# CANBUS_Pendant.net
KiCad netlist of a schematic drawn in Altium Designer
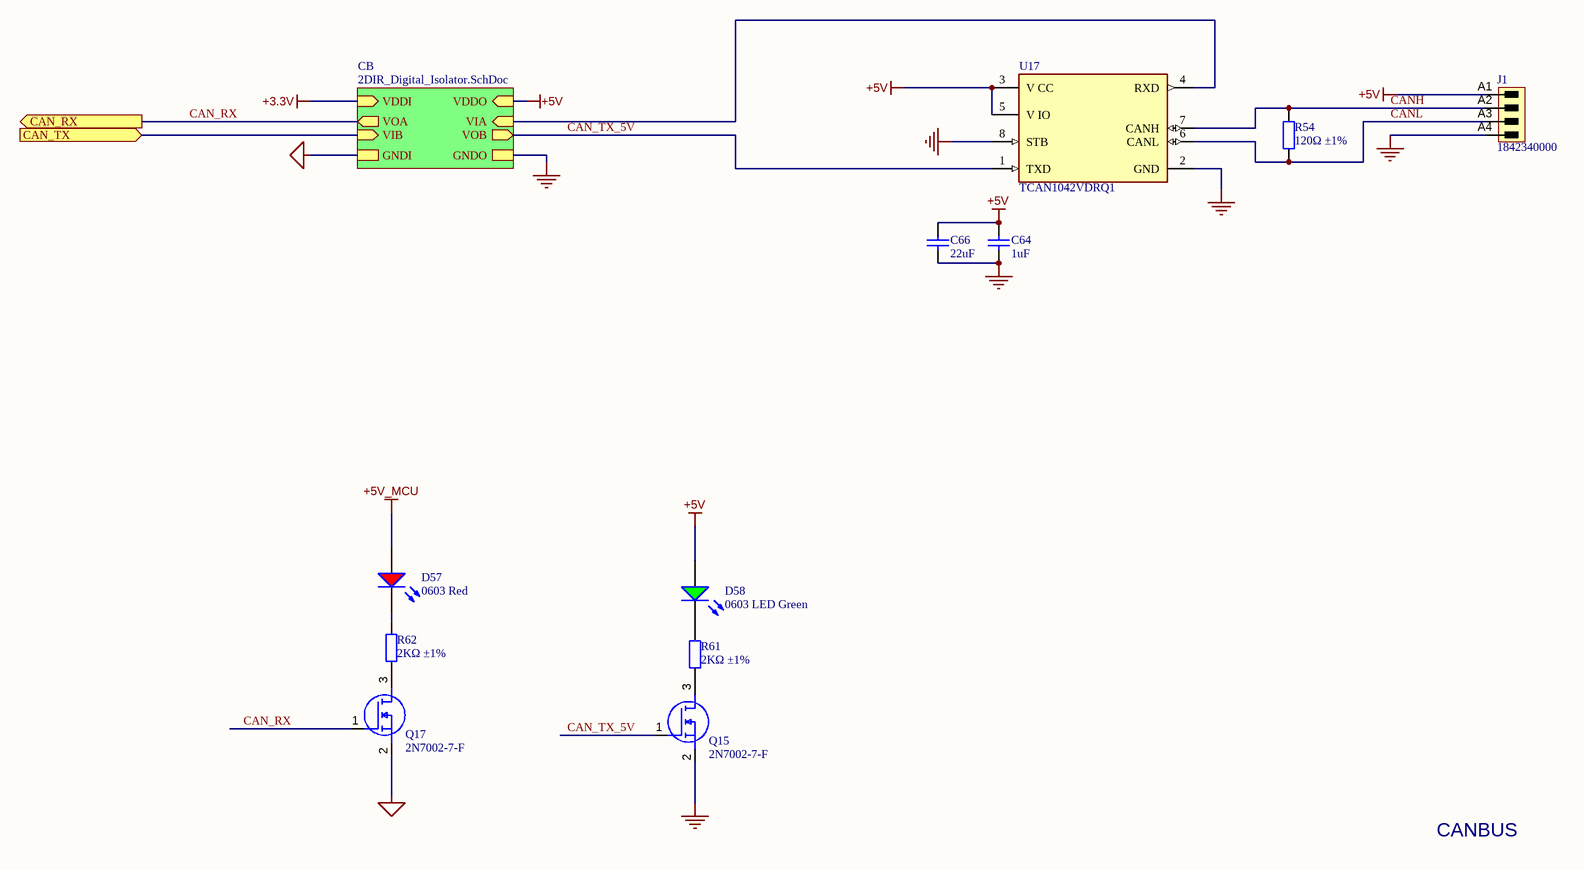
[diagram p0: CANBUS_Pendant.SchDoc]

(export (version "E")
  (design (tool "Eeschema 10.0.6"))
  (components
    (comp (ref "C64")
      (value "1uF")
      (footprint "0603_C")
      (description "Chip capacitors")
      (fields
        (field (name "MANUFACTURER") "Samsung Electro-Mechanics")
        (field (name "MANUFACTURER PART NUMBER") "CL10A105KB8NNNC")
      )
      (libsource (lib "Cap") (part "0603 1uF (105) 10% 50V"))
    )
    (comp (ref "C66")
      (value "22uF")
      (footprint "0603_C")
      (description "Chip capacitors")
      (fields
        (field (name "MANUFACTURER") "Samsung Electro-Mechanics")
        (field (name "PARTNUMBER") "CL10A226MQ8NRNC")
      )
      (libsource (lib "Cap") (part "0603 22uF (226) 20% 6.3V"))
    )
    (comp (ref "D57")
      (value "0603 Red")
      (footprint "0603_LED_S1")
      (fields
        (field (name "MANUFACTURER") "Everlight Elec")
        (field (name "MANUFACTURER PART NUMBER") "19-213SURC/S530-A3/TR8")
      )
      (libsource (lib "Sienci_Labs") (part "19-213SURC/S530-A3/TR8"))
    )
    (comp (ref "D58")
      (value "0603 LED Green")
      (footprint "0603_LED_S1")
      (fields
        (field (name "MANUFACTURER PART NUMBER") "19-217/GHC-YR1S2/3T")
        (field (name "MANUFACTURER") "Everlight Elec")
      )
      (libsource (lib "Sienci_Labs") (part "19-217/GHC-YR1S2/3T"))
    )
    (comp (ref "J1")
      (value "1842340000")
      (footprint "691321100004")
      (description "OMNIMATE Signal - series BL/SL 3.50")
      (libsource (lib "Universal_CNC_Breakout") (part "3.5mm Terminal Header 4p"))
    )
    (comp (ref "Q15")
      (value "2N7002-7-F")
      (footprint "SOT-23(SOT-23-3)")
      (description "60V 115mA 7.5Ω@5V,50mA 370mW N Channel SOT-23 MOSFETs ROHS")
      (fields (field (name "MANUFACTURER") "Diodes Inc.") (field (name "MOUSER PART NUMBER") "621-2N7002-F"))
      (libsource (lib "Sienci_Labs") (part "2N7002-7-F"))
    )
    (comp (ref "Q17")
      (value "2N7002-7-F")
      (footprint "SOT-23(SOT-23-3)")
      (description "60V 115mA 7.5Ω@5V,50mA 370mW N Channel SOT-23 MOSFETs ROHS")
      (fields (field (name "MANUFACTURER") "Diodes Inc.") (field (name "MOUSER PART NUMBER") "621-2N7002-F"))
      (libsource (lib "Sienci_Labs") (part "2N7002-7-F"))
    )
    (comp (ref "R54")
      (value "120Ω ±1%")
      (footprint "0805_R")
      (description "Chip resistor")
      (fields
        (field (name "MANUFACTURER") "Uniroyal Elec")
        (field (name "MANUFACTURER PART NUMBER") "0805W8F1200T5E")
      )
      (libsource (lib "RES") (part "0805 120R (1200) 1%"))
    )
    (comp (ref "R61")
      (value "2KΩ ±1%")
      (footprint "0402_R")
      (description "Chip resistor")
      (fields
        (field (name "MANUFACTURER") "Uniroyal Elec")
        (field (name "MANUFACTURER PART NUMBER") "0402WGF2001TCE")
      )
      (libsource (lib "RES") (part "0402 2K (2001) 1%"))
    )
    (comp (ref "R62")
      (value "2KΩ ±1%")
      (footprint "0402_R")
      (description "Chip resistor")
      (fields
        (field (name "MANUFACTURER") "Uniroyal Elec")
        (field (name "MANUFACTURER PART NUMBER") "0402WGF2001TCE")
      )
      (libsource (lib "RES") (part "0402 2K (2001) 1%"))
    )
    (comp (ref "U17")
      (value "TCAN1042VDRQ1")
      (footprint "FP-D0008B-IPC_C")
      (description "IC TRANSCEIVER 1/1 8SOIC")
      (libsource (lib "Altium Content Vault") (part "ca6e8fe669290d0f27a82b3cfbd1f09"))
    )
  )
  (nets
    (net (code "2") (name "+5V") (class "Default")
      (node (ref "C64") (pin "2") (pinfunction "2_2") (pintype "passive"))
      (node (ref "C66") (pin "2") (pinfunction "2_2") (pintype "passive"))
      (node (ref "D58") (pin "A") (pinfunction "A_A") (pintype "passive"))
      (node (ref "J1") (pin "A1") (pinfunction "A1_A1") (pintype "passive"))
      (node (ref "U17") (pin "3") (pinfunction "V_CC_3") (pintype "power_in"))
      (node (ref "U17") (pin "5") (pinfunction "V_IO_5") (pintype "power_in"))
    )
    (net (code "3") (name "+5V_MCU") (class "Default")
      (node (ref "D57") (pin "A") (pinfunction "A_A") (pintype "passive"))
    )
    (net (code "4") (name "/CANH") (class "Default")
      (node (ref "J1") (pin "A2") (pinfunction "A2_A2") (pintype "passive"))
      (node (ref "R54") (pin "2") (pinfunction "2_2") (pintype "passive"))
      (node (ref "U17") (pin "7") (pinfunction "CANH_7") (pintype "bidirectional"))
    )
    (net (code "5") (name "/CANL") (class "Default")
      (node (ref "J1") (pin "A3") (pinfunction "A3_A3") (pintype "passive"))
      (node (ref "R54") (pin "1") (pinfunction "1_1") (pintype "passive"))
      (node (ref "U17") (pin "6") (pinfunction "CANL_6") (pintype "bidirectional"))
    )
    (net (code "6") (name "/CAN_RX") (class "Default")
      (node (ref "Q17") (pin "1") (pinfunction "G_1") (pintype "passive"))
    )
    (net (code "8") (name "/CAN_TX_5V") (class "Default")
      (node (ref "Q15") (pin "1") (pinfunction "G_1") (pintype "passive"))
      (node (ref "U17") (pin "1") (pinfunction "TXD_1") (pintype "input"))
    )
    (net (code "9") (name "/VIA") (class "Default")
      (node (ref "U17") (pin "4") (pinfunction "RXD_4") (pintype "output"))
    )
    (net (code "10") (name "GND") (class "Default")
      (node (ref "C64") (pin "1") (pinfunction "1_1") (pintype "passive"))
      (node (ref "C66") (pin "1") (pinfunction "1_1") (pintype "passive"))
      (node (ref "J1") (pin "A4") (pinfunction "A4_A4") (pintype "passive"))
      (node (ref "Q15") (pin "2") (pinfunction "S_2") (pintype "passive"))
      (node (ref "U17") (pin "2") (pinfunction "GND_2") (pintype "power_in"))
      (node (ref "U17") (pin "8") (pinfunction "STB_8") (pintype "input"))
    )
    (net (code "11") (name "MCU_GND") (class "Default")
      (node (ref "Q17") (pin "2") (pinfunction "S_2") (pintype "passive"))
    )
    (net (code "12") (name "Net-(D57-PadK)") (class "Default")
      (node (ref "D57") (pin "K") (pinfunction "K_K") (pintype "passive"))
      (node (ref "R62") (pin "2") (pinfunction "2_2") (pintype "passive"))
    )
    (net (code "13") (name "Net-(D58-PadK)") (class "Default")
      (node (ref "D58") (pin "K") (pinfunction "K_K") (pintype "passive"))
      (node (ref "R61") (pin "2") (pinfunction "2_2") (pintype "passive"))
    )
    (net (code "14") (name "Net-(Q15-D)") (class "Default")
      (node (ref "Q15") (pin "3") (pinfunction "D_3") (pintype "passive"))
      (node (ref "R61") (pin "1") (pinfunction "1_1") (pintype "passive"))
    )
    (net (code "15") (name "Net-(Q17-D)") (class "Default")
      (node (ref "Q17") (pin "3") (pinfunction "D_3") (pintype "passive"))
      (node (ref "R62") (pin "1") (pinfunction "1_1") (pintype "passive"))
    )
  )
)
